# expander.net
KiCad netlist of a schematic drawn in EAGLE
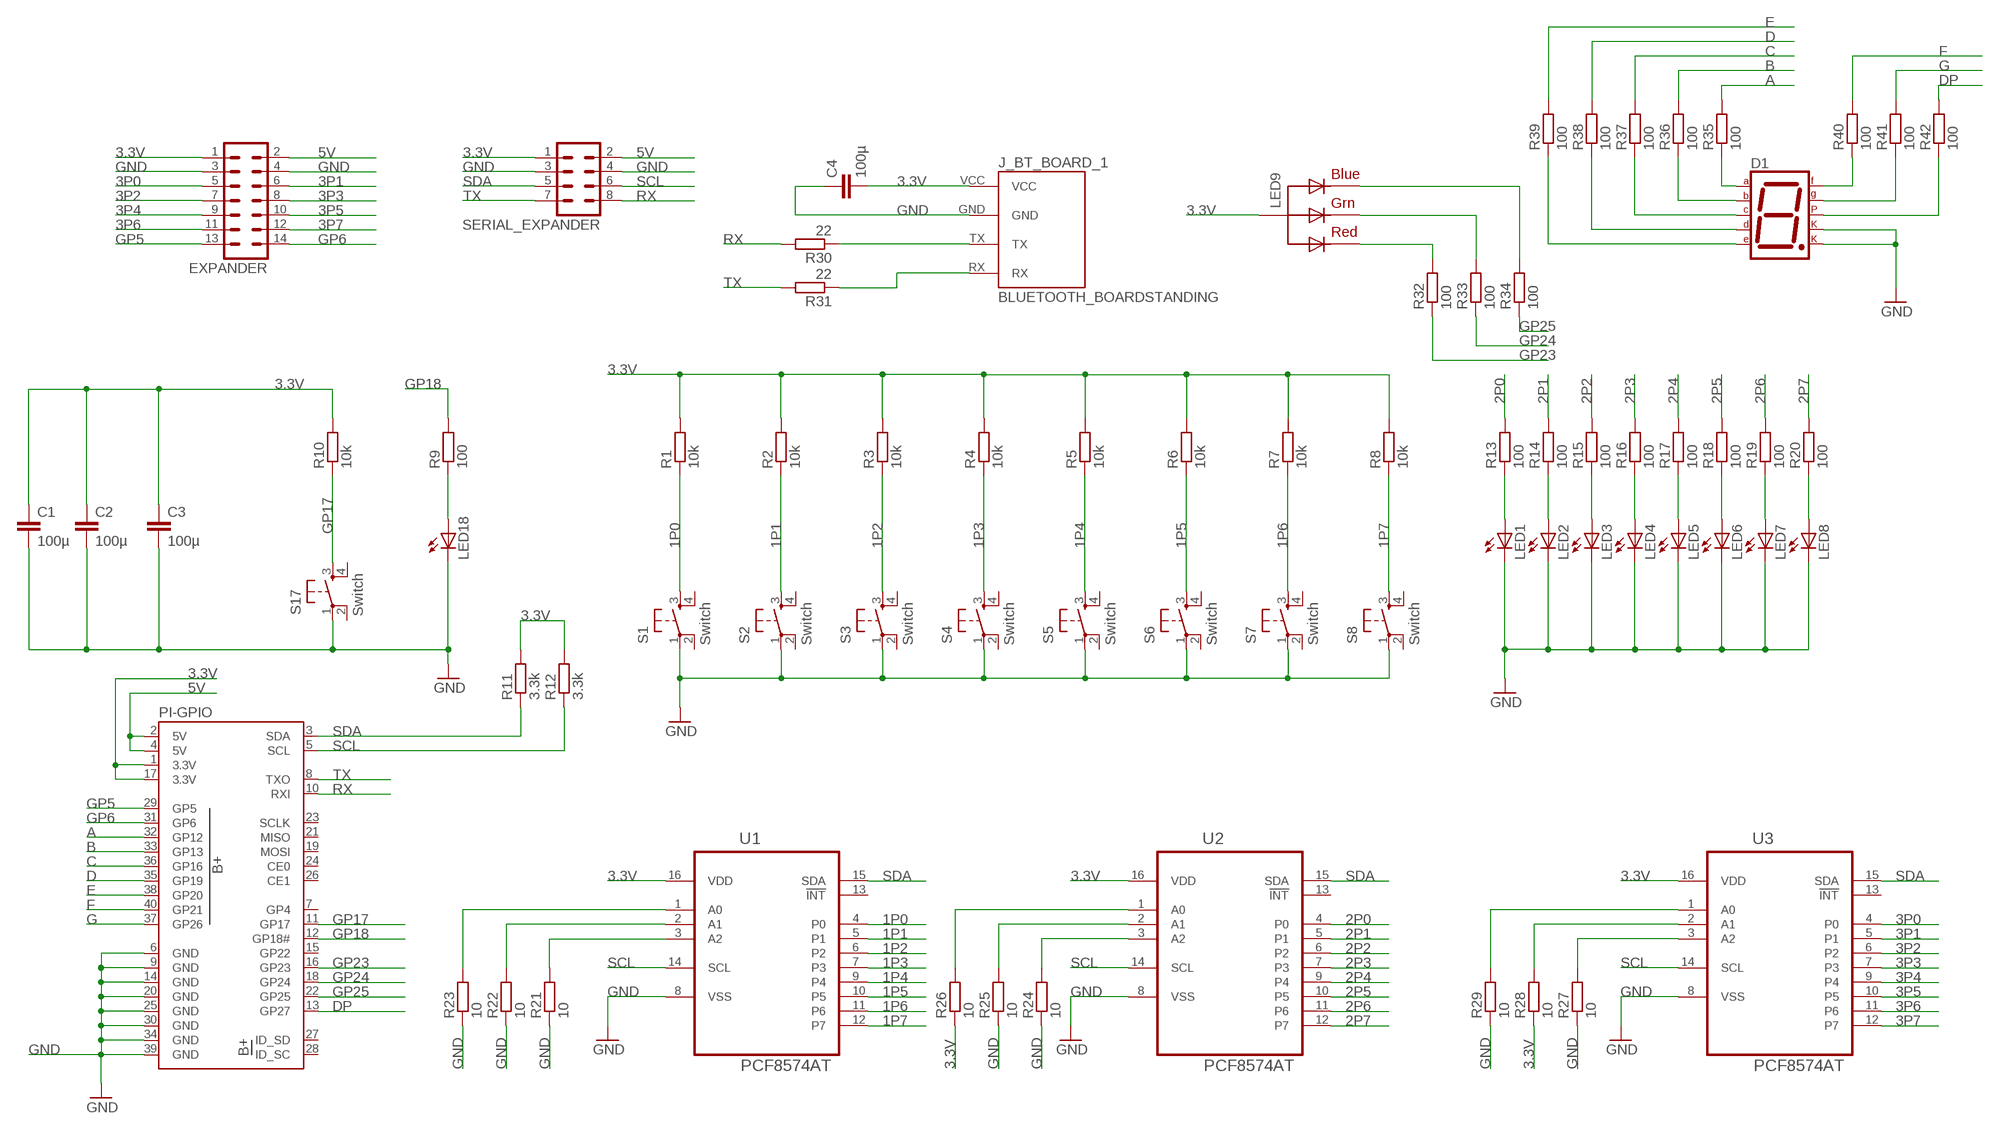
[diagram p0: schematic, sheet 1]

(export (version "E")
  (design (tool "Eeschema 10.0.6"))
  (components
    (comp (ref "C1")
      (value "100µ")
      (footprint "eagle-import:C0805")
      (libsource (lib "eagle-import") (part "C-EUC0805"))
    )
    (comp (ref "C2")
      (value "100µ")
      (footprint "eagle-import:C0805")
      (libsource (lib "eagle-import") (part "C-EUC0805"))
    )
    (comp (ref "C3")
      (value "100µ")
      (footprint "eagle-import:C0805")
      (libsource (lib "eagle-import") (part "C-EUC0805"))
    )
    (comp (ref "C4")
      (value "100µ")
      (footprint "eagle-import:C0805")
      (libsource (lib "eagle-import") (part "C-EUC0805"))
    )
    (comp (ref "D1")
      (value "7SEG-CK")
      (footprint "eagle-import:7SEG-13")
      (libsource (lib "eagle-import") (part "7SEG-CK"))
    )
    (comp (ref "EXPANDER")
      (value "MA07-2")
      (footprint "eagle-import:MA07-2")
      (libsource (lib "eagle-import") (part "MA07-2"))
    )
    (comp (ref "J_BT_BOARD_1")
      (value "BLUETOOTH_BOARDSTANDING")
      (footprint "eagle-import:BT_BOARD_FOOTPRINT_STANDING")
      (libsource (lib "eagle-import") (part "BLUETOOTH_BOARDSTANDING"))
    )
    (comp (ref "LED1")
      (value "LEDCHIP-LED0805")
      (footprint "eagle-import:CHIP-LED0805")
      (libsource (lib "eagle-import") (part "LEDCHIP-LED0805"))
    )
    (comp (ref "LED2")
      (value "LEDCHIP-LED0805")
      (footprint "eagle-import:CHIP-LED0805")
      (libsource (lib "eagle-import") (part "LEDCHIP-LED0805"))
    )
    (comp (ref "LED3")
      (value "LEDCHIP-LED0805")
      (footprint "eagle-import:CHIP-LED0805")
      (libsource (lib "eagle-import") (part "LEDCHIP-LED0805"))
    )
    (comp (ref "LED4")
      (value "LEDCHIP-LED0805")
      (footprint "eagle-import:CHIP-LED0805")
      (libsource (lib "eagle-import") (part "LEDCHIP-LED0805"))
    )
    (comp (ref "LED5")
      (value "LEDCHIP-LED0805")
      (footprint "eagle-import:CHIP-LED0805")
      (libsource (lib "eagle-import") (part "LEDCHIP-LED0805"))
    )
    (comp (ref "LED6")
      (value "LEDCHIP-LED0805")
      (footprint "eagle-import:CHIP-LED0805")
      (libsource (lib "eagle-import") (part "LEDCHIP-LED0805"))
    )
    (comp (ref "LED7")
      (value "LEDCHIP-LED0805")
      (footprint "eagle-import:CHIP-LED0805")
      (libsource (lib "eagle-import") (part "LEDCHIP-LED0805"))
    )
    (comp (ref "LED8")
      (value "LEDCHIP-LED0805")
      (footprint "eagle-import:CHIP-LED0805")
      (libsource (lib "eagle-import") (part "LEDCHIP-LED0805"))
    )
    (comp (ref "LED9")
      (value "RGBLED_CA-5MM")
      (footprint "eagle-import:LED5MMRGB")
      (libsource (lib "eagle-import") (part "RGBLED_CA-5MM"))
    )
    (comp (ref "LED18")
      (value "LEDCHIP-LED0805")
      (footprint "eagle-import:CHIP-LED0805")
      (libsource (lib "eagle-import") (part "LEDCHIP-LED0805"))
    )
    (comp (ref "PI-GPIO")
      (value "RASPBERRYPI-B+-GPIO")
      (footprint "eagle-import:2X20-SHROUDED")
      (libsource (lib "eagle-import") (part "RASPBERRYPI-B+-GPIO"))
    )
    (comp (ref "R1")
      (value "10k")
      (footprint "eagle-import:R0805")
      (libsource (lib "eagle-import") (part "R-EU_R0805"))
    )
    (comp (ref "R2")
      (value "10k")
      (footprint "eagle-import:R0805")
      (libsource (lib "eagle-import") (part "R-EU_R0805"))
    )
    (comp (ref "R3")
      (value "10k")
      (footprint "eagle-import:R0805")
      (libsource (lib "eagle-import") (part "R-EU_R0805"))
    )
    (comp (ref "R4")
      (value "10k")
      (footprint "eagle-import:R0805")
      (libsource (lib "eagle-import") (part "R-EU_R0805"))
    )
    (comp (ref "R5")
      (value "10k")
      (footprint "eagle-import:R0805")
      (libsource (lib "eagle-import") (part "R-EU_R0805"))
    )
    (comp (ref "R6")
      (value "10k")
      (footprint "eagle-import:R0805")
      (libsource (lib "eagle-import") (part "R-EU_R0805"))
    )
    (comp (ref "R7")
      (value "10k")
      (footprint "eagle-import:R0805")
      (libsource (lib "eagle-import") (part "R-EU_R0805"))
    )
    (comp (ref "R8")
      (value "10k")
      (footprint "eagle-import:R0805")
      (libsource (lib "eagle-import") (part "R-EU_R0805"))
    )
    (comp (ref "R9")
      (value "100")
      (footprint "eagle-import:R0805")
      (libsource (lib "eagle-import") (part "R-EU_R0805"))
    )
    (comp (ref "R10")
      (value "10k")
      (footprint "eagle-import:R0805")
      (libsource (lib "eagle-import") (part "R-EU_R0805"))
    )
    (comp (ref "R11")
      (value "3.3k")
      (footprint "eagle-import:R0805")
      (libsource (lib "eagle-import") (part "R-EU_R0805"))
    )
    (comp (ref "R12")
      (value "3.3k")
      (footprint "eagle-import:R0805")
      (libsource (lib "eagle-import") (part "R-EU_R0805"))
    )
    (comp (ref "R13")
      (value "100")
      (footprint "eagle-import:R0805")
      (libsource (lib "eagle-import") (part "R-EU_R0805"))
    )
    (comp (ref "R14")
      (value "100")
      (footprint "eagle-import:R0805")
      (libsource (lib "eagle-import") (part "R-EU_R0805"))
    )
    (comp (ref "R15")
      (value "100")
      (footprint "eagle-import:R0805")
      (libsource (lib "eagle-import") (part "R-EU_R0805"))
    )
    (comp (ref "R16")
      (value "100")
      (footprint "eagle-import:R0805")
      (libsource (lib "eagle-import") (part "R-EU_R0805"))
    )
    (comp (ref "R17")
      (value "100")
      (footprint "eagle-import:R0805")
      (libsource (lib "eagle-import") (part "R-EU_R0805"))
    )
    (comp (ref "R18")
      (value "100")
      (footprint "eagle-import:R0805")
      (libsource (lib "eagle-import") (part "R-EU_R0805"))
    )
    (comp (ref "R19")
      (value "100")
      (footprint "eagle-import:R0805")
      (libsource (lib "eagle-import") (part "R-EU_R0805"))
    )
    (comp (ref "R20")
      (value "100")
      (footprint "eagle-import:R0805")
      (libsource (lib "eagle-import") (part "R-EU_R0805"))
    )
    (comp (ref "R21")
      (value "10")
      (footprint "eagle-import:R0805")
      (libsource (lib "eagle-import") (part "R-EU_R0805"))
    )
    (comp (ref "R22")
      (value "10")
      (footprint "eagle-import:R0805")
      (libsource (lib "eagle-import") (part "R-EU_R0805"))
    )
    (comp (ref "R23")
      (value "10")
      (footprint "eagle-import:R0805")
      (libsource (lib "eagle-import") (part "R-EU_R0805"))
    )
    (comp (ref "R24")
      (value "10")
      (footprint "eagle-import:R0805")
      (libsource (lib "eagle-import") (part "R-EU_R0805"))
    )
    (comp (ref "R25")
      (value "10")
      (footprint "eagle-import:R0805")
      (libsource (lib "eagle-import") (part "R-EU_R0805"))
    )
    (comp (ref "R26")
      (value "10")
      (footprint "eagle-import:R0805")
      (libsource (lib "eagle-import") (part "R-EU_R0805"))
    )
    (comp (ref "R27")
      (value "10")
      (footprint "eagle-import:R0805")
      (libsource (lib "eagle-import") (part "R-EU_R0805"))
    )
    (comp (ref "R28")
      (value "10")
      (footprint "eagle-import:R0805")
      (libsource (lib "eagle-import") (part "R-EU_R0805"))
    )
    (comp (ref "R29")
      (value "10")
      (footprint "eagle-import:R0805")
      (libsource (lib "eagle-import") (part "R-EU_R0805"))
    )
    (comp (ref "R30")
      (value "22")
      (footprint "eagle-import:R0805")
      (libsource (lib "eagle-import") (part "R-EU_R0805"))
    )
    (comp (ref "R31")
      (value "22")
      (footprint "eagle-import:R0805")
      (libsource (lib "eagle-import") (part "R-EU_R0805"))
    )
    (comp (ref "R32")
      (value "100")
      (footprint "eagle-import:R0805")
      (libsource (lib "eagle-import") (part "R-EU_R0805"))
    )
    (comp (ref "R33")
      (value "100")
      (footprint "eagle-import:R0805")
      (libsource (lib "eagle-import") (part "R-EU_R0805"))
    )
    (comp (ref "R34")
      (value "100")
      (footprint "eagle-import:R0805")
      (libsource (lib "eagle-import") (part "R-EU_R0805"))
    )
    (comp (ref "R35")
      (value "100")
      (footprint "eagle-import:R0805")
      (libsource (lib "eagle-import") (part "R-EU_R0805"))
    )
    (comp (ref "R36")
      (value "100")
      (footprint "eagle-import:R0805")
      (libsource (lib "eagle-import") (part "R-EU_R0805"))
    )
    (comp (ref "R37")
      (value "100")
      (footprint "eagle-import:R0805")
      (libsource (lib "eagle-import") (part "R-EU_R0805"))
    )
    (comp (ref "R38")
      (value "100")
      (footprint "eagle-import:R0805")
      (libsource (lib "eagle-import") (part "R-EU_R0805"))
    )
    (comp (ref "R39")
      (value "100")
      (footprint "eagle-import:R0805")
      (libsource (lib "eagle-import") (part "R-EU_R0805"))
    )
    (comp (ref "R40")
      (value "100")
      (footprint "eagle-import:R0805")
      (libsource (lib "eagle-import") (part "R-EU_R0805"))
    )
    (comp (ref "R41")
      (value "100")
      (footprint "eagle-import:R0805")
      (libsource (lib "eagle-import") (part "R-EU_R0805"))
    )
    (comp (ref "R42")
      (value "100")
      (footprint "eagle-import:R0805")
      (libsource (lib "eagle-import") (part "R-EU_R0805"))
    )
    (comp (ref "S1")
      (value "Switch")
      (footprint "eagle-import:TAC-SWITCH-PTH")
      (libsource (lib "eagle-import") (part "TACTILE-SWITCH-PTH"))
    )
    (comp (ref "S2")
      (value "Switch")
      (footprint "eagle-import:TAC-SWITCH-PTH")
      (libsource (lib "eagle-import") (part "TACTILE-SWITCH-PTH"))
    )
    (comp (ref "S3")
      (value "Switch")
      (footprint "eagle-import:TAC-SWITCH-PTH")
      (libsource (lib "eagle-import") (part "TACTILE-SWITCH-PTH"))
    )
    (comp (ref "S4")
      (value "Switch")
      (footprint "eagle-import:TAC-SWITCH-PTH")
      (libsource (lib "eagle-import") (part "TACTILE-SWITCH-PTH"))
    )
    (comp (ref "S5")
      (value "Switch")
      (footprint "eagle-import:TAC-SWITCH-PTH")
      (libsource (lib "eagle-import") (part "TACTILE-SWITCH-PTH"))
    )
    (comp (ref "S6")
      (value "Switch")
      (footprint "eagle-import:TAC-SWITCH-PTH")
      (libsource (lib "eagle-import") (part "TACTILE-SWITCH-PTH"))
    )
    (comp (ref "S7")
      (value "Switch")
      (footprint "eagle-import:TAC-SWITCH-PTH")
      (libsource (lib "eagle-import") (part "TACTILE-SWITCH-PTH"))
    )
    (comp (ref "S8")
      (value "Switch")
      (footprint "eagle-import:TAC-SWITCH-PTH")
      (libsource (lib "eagle-import") (part "TACTILE-SWITCH-PTH"))
    )
    (comp (ref "S17")
      (value "Switch")
      (footprint "eagle-import:TAC-SWITCH-PTH")
      (libsource (lib "eagle-import") (part "TACTILE-SWITCH-PTH"))
    )
    (comp (ref "SERIAL_EXPANDER")
      (value "MA04-2")
      (footprint "eagle-import:MA04-2")
      (libsource (lib "eagle-import") (part "MA04-2"))
    )
    (comp (ref "U1")
      (value "PCF8574AT")
      (footprint "eagle-import:SOIC127P1032X265-16N")
      (fields (field (name "MPN") "PCF8574AT/3,512"))
      (libsource (lib "eagle-import") (part "PCF8574AT/3,512"))
    )
    (comp (ref "U2")
      (value "PCF8574AT")
      (footprint "eagle-import:SOIC127P1032X265-16N")
      (fields (field (name "MPN") "PCF8574AT/3,512"))
      (libsource (lib "eagle-import") (part "PCF8574AT/3,512"))
    )
    (comp (ref "U3")
      (value "PCF8574AT")
      (footprint "eagle-import:SOIC127P1032X265-16N")
      (fields (field (name "MPN") "PCF8574AT/3,512"))
      (libsource (lib "eagle-import") (part "PCF8574AT/3,512"))
    )
  )
  (nets
    (net (code "1") (name "/1P0") (class "Default")
      (node (ref "R1") (pin "1") (pinfunction "1_1") (pintype "passive"))
      (node (ref "S1") (pin "3") (pinfunction "3_3") (pintype "passive"))
      (node (ref "U1") (pin "4") (pinfunction "P0_4") (pintype "bidirectional"))
    )
    (net (code "2") (name "/1P1") (class "Default")
      (node (ref "R2") (pin "1") (pinfunction "1_1") (pintype "passive"))
      (node (ref "S2") (pin "3") (pinfunction "3_3") (pintype "passive"))
      (node (ref "U1") (pin "5") (pinfunction "P1_5") (pintype "bidirectional"))
    )
    (net (code "3") (name "/1P2") (class "Default")
      (node (ref "R3") (pin "1") (pinfunction "1_1") (pintype "passive"))
      (node (ref "S3") (pin "3") (pinfunction "3_3") (pintype "passive"))
      (node (ref "U1") (pin "6") (pinfunction "P2_6") (pintype "bidirectional"))
    )
    (net (code "4") (name "/1P3") (class "Default")
      (node (ref "R4") (pin "1") (pinfunction "1_1") (pintype "passive"))
      (node (ref "S4") (pin "3") (pinfunction "3_3") (pintype "passive"))
      (node (ref "U1") (pin "7") (pinfunction "P3_7") (pintype "bidirectional"))
    )
    (net (code "5") (name "/1P4") (class "Default")
      (node (ref "R5") (pin "1") (pinfunction "1_1") (pintype "passive"))
      (node (ref "S5") (pin "3") (pinfunction "3_3") (pintype "passive"))
      (node (ref "U1") (pin "9") (pinfunction "P4_9") (pintype "bidirectional"))
    )
    (net (code "6") (name "/1P5") (class "Default")
      (node (ref "R6") (pin "1") (pinfunction "1_1") (pintype "passive"))
      (node (ref "S6") (pin "3") (pinfunction "3_3") (pintype "passive"))
      (node (ref "U1") (pin "10") (pinfunction "P5_10") (pintype "bidirectional"))
    )
    (net (code "7") (name "/1P6") (class "Default")
      (node (ref "R7") (pin "1") (pinfunction "1_1") (pintype "passive"))
      (node (ref "S7") (pin "3") (pinfunction "3_3") (pintype "passive"))
      (node (ref "U1") (pin "11") (pinfunction "P6_11") (pintype "bidirectional"))
    )
    (net (code "8") (name "/1P7") (class "Default")
      (node (ref "R8") (pin "1") (pinfunction "1_1") (pintype "passive"))
      (node (ref "S8") (pin "3") (pinfunction "3_3") (pintype "passive"))
      (node (ref "U1") (pin "12") (pinfunction "P7_12") (pintype "bidirectional"))
    )
    (net (code "9") (name "/2P0") (class "Default")
      (node (ref "R13") (pin "2") (pinfunction "2_2") (pintype "passive"))
      (node (ref "U2") (pin "4") (pinfunction "P0_4") (pintype "bidirectional"))
    )
    (net (code "10") (name "/2P1") (class "Default")
      (node (ref "R14") (pin "2") (pinfunction "2_2") (pintype "passive"))
      (node (ref "U2") (pin "5") (pinfunction "P1_5") (pintype "bidirectional"))
    )
    (net (code "11") (name "/2P2") (class "Default")
      (node (ref "R15") (pin "2") (pinfunction "2_2") (pintype "passive"))
      (node (ref "U2") (pin "6") (pinfunction "P2_6") (pintype "bidirectional"))
    )
    (net (code "12") (name "/2P3") (class "Default")
      (node (ref "R16") (pin "2") (pinfunction "2_2") (pintype "passive"))
      (node (ref "U2") (pin "7") (pinfunction "P3_7") (pintype "bidirectional"))
    )
    (net (code "13") (name "/2P4") (class "Default")
      (node (ref "R17") (pin "2") (pinfunction "2_2") (pintype "passive"))
      (node (ref "U2") (pin "9") (pinfunction "P4_9") (pintype "bidirectional"))
    )
    (net (code "14") (name "/2P5") (class "Default")
      (node (ref "R18") (pin "2") (pinfunction "2_2") (pintype "passive"))
      (node (ref "U2") (pin "10") (pinfunction "P5_10") (pintype "bidirectional"))
    )
    (net (code "15") (name "/2P6") (class "Default")
      (node (ref "R19") (pin "2") (pinfunction "2_2") (pintype "passive"))
      (node (ref "U2") (pin "11") (pinfunction "P6_11") (pintype "bidirectional"))
    )
    (net (code "16") (name "/2P7") (class "Default")
      (node (ref "R20") (pin "2") (pinfunction "2_2") (pintype "passive"))
      (node (ref "U2") (pin "12") (pinfunction "P7_12") (pintype "bidirectional"))
    )
    (net (code "17") (name "/3.3V") (class "Default")
      (node (ref "C1") (pin "1") (pinfunction "1_1") (pintype "passive"))
      (node (ref "C2") (pin "1") (pinfunction "1_1") (pintype "passive"))
      (node (ref "C3") (pin "1") (pinfunction "1_1") (pintype "passive"))
      (node (ref "C4") (pin "2") (pinfunction "2_2") (pintype "passive"))
      (node (ref "EXPANDER") (pin "1") (pinfunction "1_1") (pintype "passive"))
      (node (ref "J_BT_BOARD_1") (pin "VCC") (pinfunction "VCC_VCC") (pintype "bidirectional"))
      (node (ref "LED9") (pin "2") (pinfunction "VCC_2") (pintype "bidirectional"))
      (node (ref "PI-GPIO") (pin "1") (pinfunction "3.3V_1") (pintype "power_in"))
      (node (ref "PI-GPIO") (pin "17") (pinfunction "3.3V_17") (pintype "power_in"))
      (node (ref "R1") (pin "2") (pinfunction "2_2") (pintype "passive"))
      (node (ref "R10") (pin "2") (pinfunction "2_2") (pintype "passive"))
      (node (ref "R11") (pin "2") (pinfunction "2_2") (pintype "passive"))
      (node (ref "R12") (pin "2") (pinfunction "2_2") (pintype "passive"))
      (node (ref "R2") (pin "2") (pinfunction "2_2") (pintype "passive"))
      (node (ref "R26") (pin "1") (pinfunction "1_1") (pintype "passive"))
      (node (ref "R28") (pin "1") (pinfunction "1_1") (pintype "passive"))
      (node (ref "R3") (pin "2") (pinfunction "2_2") (pintype "passive"))
      (node (ref "R4") (pin "2") (pinfunction "2_2") (pintype "passive"))
      (node (ref "R5") (pin "2") (pinfunction "2_2") (pintype "passive"))
      (node (ref "R6") (pin "2") (pinfunction "2_2") (pintype "passive"))
      (node (ref "R7") (pin "2") (pinfunction "2_2") (pintype "passive"))
      (node (ref "R8") (pin "2") (pinfunction "2_2") (pintype "passive"))
      (node (ref "SERIAL_EXPANDER") (pin "1") (pinfunction "1_1") (pintype "passive"))
      (node (ref "U1") (pin "16") (pinfunction "VDD_16") (pintype "power_in"))
      (node (ref "U2") (pin "16") (pinfunction "VDD_16") (pintype "power_in"))
      (node (ref "U3") (pin "16") (pinfunction "VDD_16") (pintype "power_in"))
    )
    (net (code "18") (name "/3P0") (class "Default")
      (node (ref "EXPANDER") (pin "5") (pinfunction "5_5") (pintype "passive"))
      (node (ref "U3") (pin "4") (pinfunction "P0_4") (pintype "bidirectional"))
    )
    (net (code "19") (name "/3P1") (class "Default")
      (node (ref "EXPANDER") (pin "6") (pinfunction "6_6") (pintype "passive"))
      (node (ref "U3") (pin "5") (pinfunction "P1_5") (pintype "bidirectional"))
    )
    (net (code "20") (name "/3P2") (class "Default")
      (node (ref "EXPANDER") (pin "7") (pinfunction "7_7") (pintype "passive"))
      (node (ref "U3") (pin "6") (pinfunction "P2_6") (pintype "bidirectional"))
    )
    (net (code "21") (name "/3P3") (class "Default")
      (node (ref "EXPANDER") (pin "8") (pinfunction "8_8") (pintype "passive"))
      (node (ref "U3") (pin "7") (pinfunction "P3_7") (pintype "bidirectional"))
    )
    (net (code "22") (name "/3P4") (class "Default")
      (node (ref "EXPANDER") (pin "9") (pinfunction "9_9") (pintype "passive"))
      (node (ref "U3") (pin "9") (pinfunction "P4_9") (pintype "bidirectional"))
    )
    (net (code "23") (name "/3P5") (class "Default")
      (node (ref "EXPANDER") (pin "10") (pinfunction "10_10") (pintype "passive"))
      (node (ref "U3") (pin "10") (pinfunction "P5_10") (pintype "bidirectional"))
    )
    (net (code "24") (name "/3P6") (class "Default")
      (node (ref "EXPANDER") (pin "11") (pinfunction "11_11") (pintype "passive"))
      (node (ref "U3") (pin "11") (pinfunction "P6_11") (pintype "bidirectional"))
    )
    (net (code "25") (name "/3P7") (class "Default")
      (node (ref "EXPANDER") (pin "12") (pinfunction "12_12") (pintype "passive"))
      (node (ref "U3") (pin "12") (pinfunction "P7_12") (pintype "bidirectional"))
    )
    (net (code "26") (name "/5V") (class "Default")
      (node (ref "EXPANDER") (pin "2") (pinfunction "2_2") (pintype "passive"))
      (node (ref "PI-GPIO") (pin "2") (pinfunction "5V_2") (pintype "power_in"))
      (node (ref "PI-GPIO") (pin "4") (pinfunction "5V_4") (pintype "power_in"))
      (node (ref "SERIAL_EXPANDER") (pin "2") (pinfunction "2_2") (pintype "passive"))
    )
    (net (code "27") (name "/A") (class "Default")
      (node (ref "PI-GPIO") (pin "32") (pinfunction "GP12_32") (pintype "bidirectional"))
      (node (ref "R35") (pin "2") (pinfunction "2_2") (pintype "passive"))
    )
    (net (code "28") (name "/B") (class "Default")
      (node (ref "PI-GPIO") (pin "33") (pinfunction "GP13_33") (pintype "bidirectional"))
      (node (ref "R36") (pin "2") (pinfunction "2_2") (pintype "passive"))
    )
    (net (code "29") (name "/C") (class "Default")
      (node (ref "PI-GPIO") (pin "36") (pinfunction "GP16_36") (pintype "bidirectional"))
      (node (ref "R37") (pin "2") (pinfunction "2_2") (pintype "passive"))
    )
    (net (code "30") (name "/D") (class "Default")
      (node (ref "PI-GPIO") (pin "35") (pinfunction "GP19_35") (pintype "bidirectional"))
      (node (ref "R38") (pin "2") (pinfunction "2_2") (pintype "passive"))
    )
    (net (code "31") (name "/DP") (class "Default")
      (node (ref "PI-GPIO") (pin "13") (pinfunction "GP27_13") (pintype "bidirectional"))
      (node (ref "R42") (pin "2") (pinfunction "2_2") (pintype "passive"))
    )
    (net (code "32") (name "/E") (class "Default")
      (node (ref "PI-GPIO") (pin "38") (pinfunction "GP20_38") (pintype "bidirectional"))
      (node (ref "R39") (pin "2") (pinfunction "2_2") (pintype "passive"))
    )
    (net (code "33") (name "/F") (class "Default")
      (node (ref "PI-GPIO") (pin "40") (pinfunction "GP21_40") (pintype "bidirectional"))
      (node (ref "R40") (pin "2") (pinfunction "2_2") (pintype "passive"))
    )
    (net (code "34") (name "/G") (class "Default")
      (node (ref "PI-GPIO") (pin "37") (pinfunction "GP26_37") (pintype "bidirectional"))
      (node (ref "R41") (pin "2") (pinfunction "2_2") (pintype "passive"))
    )
    (net (code "35") (name "/GP5") (class "Default")
      (node (ref "EXPANDER") (pin "13") (pinfunction "13_13") (pintype "passive"))
      (node (ref "PI-GPIO") (pin "29") (pinfunction "GP5_29") (pintype "bidirectional"))
    )
    (net (code "36") (name "/GP6") (class "Default")
      (node (ref "EXPANDER") (pin "14") (pinfunction "14_14") (pintype "passive"))
      (node (ref "PI-GPIO") (pin "31") (pinfunction "GP6_31") (pintype "bidirectional"))
    )
    (net (code "37") (name "/GP17") (class "Default")
      (node (ref "PI-GPIO") (pin "11") (pinfunction "GP17_11") (pintype "bidirectional"))
      (node (ref "R10") (pin "1") (pinfunction "1_1") (pintype "passive"))
      (node (ref "S17") (pin "3") (pinfunction "3_3") (pintype "passive"))
    )
    (net (code "38") (name "/GP18") (class "Default")
      (node (ref "PI-GPIO") (pin "12") (pinfunction "GP18#_12") (pintype "bidirectional"))
      (node (ref "R9") (pin "2") (pinfunction "2_2") (pintype "passive"))
    )
    (net (code "39") (name "/GP23") (class "Default")
      (node (ref "PI-GPIO") (pin "16") (pinfunction "GP23_16") (pintype "bidirectional"))
      (node (ref "R32") (pin "1") (pinfunction "1_1") (pintype "passive"))
    )
    (net (code "40") (name "/GP24") (class "Default")
      (node (ref "PI-GPIO") (pin "18") (pinfunction "GP24_18") (pintype "bidirectional"))
      (node (ref "R33") (pin "1") (pinfunction "1_1") (pintype "passive"))
    )
    (net (code "41") (name "/GP25") (class "Default")
      (node (ref "PI-GPIO") (pin "22") (pinfunction "GP25_22") (pintype "bidirectional"))
      (node (ref "R34") (pin "1") (pinfunction "1_1") (pintype "passive"))
    )
    (net (code "42") (name "/RX") (class "Default")
      (node (ref "PI-GPIO") (pin "10") (pinfunction "RXI_10") (pintype "input"))
      (node (ref "R30") (pin "2") (pinfunction "2_2") (pintype "passive"))
      (node (ref "SERIAL_EXPANDER") (pin "8") (pinfunction "8_8") (pintype "passive"))
    )
    (net (code "43") (name "/SCL") (class "Default")
      (node (ref "PI-GPIO") (pin "5") (pinfunction "SCL_5") (pintype "bidirectional"))
      (node (ref "R12") (pin "1") (pinfunction "1_1") (pintype "passive"))
      (node (ref "SERIAL_EXPANDER") (pin "6") (pinfunction "6_6") (pintype "passive"))
      (node (ref "U1") (pin "14") (pinfunction "SCL_14") (pintype "input"))
      (node (ref "U2") (pin "14") (pinfunction "SCL_14") (pintype "input"))
      (node (ref "U3") (pin "14") (pinfunction "SCL_14") (pintype "input"))
    )
    (net (code "44") (name "/SDA") (class "Default")
      (node (ref "PI-GPIO") (pin "3") (pinfunction "SDA_3") (pintype "bidirectional"))
      (node (ref "R11") (pin "1") (pinfunction "1_1") (pintype "passive"))
      (node (ref "SERIAL_EXPANDER") (pin "5") (pinfunction "5_5") (pintype "passive"))
      (node (ref "U1") (pin "15") (pinfunction "SDA_15") (pintype "bidirectional"))
      (node (ref "U2") (pin "15") (pinfunction "SDA_15") (pintype "bidirectional"))
      (node (ref "U3") (pin "15") (pinfunction "SDA_15") (pintype "bidirectional"))
    )
    (net (code "45") (name "/TX") (class "Default")
      (node (ref "PI-GPIO") (pin "8") (pinfunction "TXO_8") (pintype "output"))
      (node (ref "R31") (pin "2") (pinfunction "2_2") (pintype "passive"))
      (node (ref "SERIAL_EXPANDER") (pin "7") (pinfunction "7_7") (pintype "passive"))
    )
    (net (code "46") (name "GND") (class "Default")
      (node (ref "C1") (pin "2") (pinfunction "2_2") (pintype "passive"))
      (node (ref "C2") (pin "2") (pinfunction "2_2") (pintype "passive"))
      (node (ref "C3") (pin "2") (pinfunction "2_2") (pintype "passive"))
      (node (ref "C4") (pin "1") (pinfunction "1_1") (pintype "passive"))
      (node (ref "D1") (pin "3") (pinfunction "CK1_3") (pintype "passive"))
      (node (ref "D1") (pin "8") (pinfunction "CK2_8") (pintype "passive"))
      (node (ref "EXPANDER") (pin "3") (pinfunction "3_3") (pintype "passive"))
      (node (ref "EXPANDER") (pin "4") (pinfunction "4_4") (pintype "passive"))
      (node (ref "J_BT_BOARD_1") (pin "GND") (pinfunction "GND_GND") (pintype "bidirectional"))
      (node (ref "LED1") (pin "C") (pinfunction "C_C") (pintype "passive"))
      (node (ref "LED18") (pin "C") (pinfunction "C_C") (pintype "passive"))
      (node (ref "LED2") (pin "C") (pinfunction "C_C") (pintype "passive"))
      (node (ref "LED3") (pin "C") (pinfunction "C_C") (pintype "passive"))
      (node (ref "LED4") (pin "C") (pinfunction "C_C") (pintype "passive"))
      (node (ref "LED5") (pin "C") (pinfunction "C_C") (pintype "passive"))
      (node (ref "LED6") (pin "C") (pinfunction "C_C") (pintype "passive"))
      (node (ref "LED7") (pin "C") (pinfunction "C_C") (pintype "passive"))
      (node (ref "LED8") (pin "C") (pinfunction "C_C") (pintype "passive"))
      (node (ref "PI-GPIO") (pin "14") (pinfunction "GND_14") (pintype "power_in"))
      (node (ref "PI-GPIO") (pin "20") (pinfunction "GND_20") (pintype "power_in"))
      (node (ref "PI-GPIO") (pin "25") (pinfunction "GND_25") (pintype "power_in"))
      (node (ref "PI-GPIO") (pin "30") (pinfunction "GND_30") (pintype "power_in"))
      (node (ref "PI-GPIO") (pin "34") (pinfunction "GND_34") (pintype "power_in"))
      (node (ref "PI-GPIO") (pin "39") (pinfunction "GND_39") (pintype "power_in"))
      (node (ref "PI-GPIO") (pin "6") (pinfunction "GND_6") (pintype "power_in"))
      (node (ref "PI-GPIO") (pin "9") (pinfunction "GND_9") (pintype "power_in"))
      (node (ref "R21") (pin "1") (pinfunction "1_1") (pintype "passive"))
      (node (ref "R22") (pin "1") (pinfunction "1_1") (pintype "passive"))
      (node (ref "R23") (pin "1") (pinfunction "1_1") (pintype "passive"))
      (node (ref "R24") (pin "1") (pinfunction "1_1") (pintype "passive"))
      (node (ref "R25") (pin "1") (pinfunction "1_1") (pintype "passive"))
      (node (ref "R27") (pin "1") (pinfunction "1_1") (pintype "passive"))
      (node (ref "R29") (pin "1") (pinfunction "1_1") (pintype "passive"))
      (node (ref "S1") (pin "1") (pinfunction "1_1") (pintype "passive"))
      (node (ref "S17") (pin "1") (pinfunction "1_1") (pintype "passive"))
      (node (ref "S2") (pin "1") (pinfunction "1_1") (pintype "passive"))
      (node (ref "S3") (pin "1") (pinfunction "1_1") (pintype "passive"))
      (node (ref "S4") (pin "1") (pinfunction "1_1") (pintype "passive"))
      (node (ref "S5") (pin "1") (pinfunction "1_1") (pintype "passive"))
      (node (ref "S6") (pin "1") (pinfunction "1_1") (pintype "passive"))
      (node (ref "S7") (pin "1") (pinfunction "1_1") (pintype "passive"))
      (node (ref "S8") (pin "1") (pinfunction "1_1") (pintype "passive"))
      (node (ref "SERIAL_EXPANDER") (pin "3") (pinfunction "3_3") (pintype "passive"))
      (node (ref "SERIAL_EXPANDER") (pin "4") (pinfunction "4_4") (pintype "passive"))
      (node (ref "U1") (pin "8") (pinfunction "VSS_8") (pintype "passive"))
      (node (ref "U2") (pin "8") (pinfunction "VSS_8") (pintype "passive"))
      (node (ref "U3") (pin "8") (pinfunction "VSS_8") (pintype "passive"))
    )
    (net (code "47") (name "Net-(D1-A)") (class "Default")
      (node (ref "D1") (pin "7") (pinfunction "A_7") (pintype "passive"))
      (node (ref "R35") (pin "1") (pinfunction "1_1") (pintype "passive"))
    )
    (net (code "48") (name "Net-(D1-B)") (class "Default")
      (node (ref "D1") (pin "6") (pinfunction "B_6") (pintype "passive"))
      (node (ref "R36") (pin "1") (pinfunction "1_1") (pintype "passive"))
    )
    (net (code "49") (name "Net-(D1-C)") (class "Default")
      (node (ref "D1") (pin "4") (pinfunction "C_4") (pintype "passive"))
      (node (ref "R37") (pin "1") (pinfunction "1_1") (pintype "passive"))
    )
    (net (code "50") (name "Net-(D1-D)") (class "Default")
      (node (ref "D1") (pin "2") (pinfunction "D_2") (pintype "passive"))
      (node (ref "R38") (pin "1") (pinfunction "1_1") (pintype "passive"))
    )
    (net (code "51") (name "Net-(D1-DP)") (class "Default")
      (node (ref "D1") (pin "5") (pinfunction "DP_5") (pintype "passive"))
      (node (ref "R42") (pin "1") (pinfunction "1_1") (pintype "passive"))
    )
    (net (code "52") (name "Net-(D1-E)") (class "Default")
      (node (ref "D1") (pin "1") (pinfunction "E_1") (pintype "passive"))
      (node (ref "R39") (pin "1") (pinfunction "1_1") (pintype "passive"))
    )
    (net (code "53") (name "Net-(D1-F)") (class "Default")
      (node (ref "D1") (pin "9") (pinfunction "F_9") (pintype "passive"))
      (node (ref "R40") (pin "1") (pinfunction "1_1") (pintype "passive"))
    )
    (net (code "54") (name "Net-(D1-G)") (class "Default")
      (node (ref "D1") (pin "10") (pinfunction "G_10") (pintype "passive"))
      (node (ref "R41") (pin "1") (pinfunction "1_1") (pintype "passive"))
    )
    (net (code "55") (name "Net-(J_BT_BOARD_1-PadRX)") (class "Default")
      (node (ref "J_BT_BOARD_1") (pin "RX") (pinfunction "RX_RX") (pintype "bidirectional"))
      (node (ref "R31") (pin "1") (pinfunction "1_1") (pintype "passive"))
    )
    (net (code "56") (name "Net-(J_BT_BOARD_1-PadTX)") (class "Default")
      (node (ref "J_BT_BOARD_1") (pin "TX") (pinfunction "TX_TX") (pintype "bidirectional"))
      (node (ref "R30") (pin "1") (pinfunction "1_1") (pintype "passive"))
    )
    (net (code "57") (name "Net-(LED1-PadA)") (class "Default")
      (node (ref "LED1") (pin "A") (pinfunction "A_A") (pintype "passive"))
      (node (ref "R13") (pin "1") (pinfunction "1_1") (pintype "passive"))
    )
    (net (code "58") (name "Net-(LED2-PadA)") (class "Default")
      (node (ref "LED2") (pin "A") (pinfunction "A_A") (pintype "passive"))
      (node (ref "R14") (pin "1") (pinfunction "1_1") (pintype "passive"))
    )
    (net (code "59") (name "Net-(LED3-PadA)") (class "Default")
      (node (ref "LED3") (pin "A") (pinfunction "A_A") (pintype "passive"))
      (node (ref "R15") (pin "1") (pinfunction "1_1") (pintype "passive"))
    )
    (net (code "60") (name "Net-(LED4-PadA)") (class "Default")
      (node (ref "LED4") (pin "A") (pinfunction "A_A") (pintype "passive"))
      (node (ref "R16") (pin "1") (pinfunction "1_1") (pintype "passive"))
    )
    (net (code "61") (name "Net-(LED5-PadA)") (class "Default")
      (node (ref "LED5") (pin "A") (pinfunction "A_A") (pintype "passive"))
      (node (ref "R17") (pin "1") (pinfunction "1_1") (pintype "passive"))
    )
    (net (code "62") (name "Net-(LED6-PadA)") (class "Default")
      (node (ref "LED6") (pin "A") (pinfunction "A_A") (pintype "passive"))
      (node (ref "R18") (pin "1") (pinfunction "1_1") (pintype "passive"))
    )
    (net (code "63") (name "Net-(LED7-PadA)") (class "Default")
      (node (ref "LED7") (pin "A") (pinfunction "A_A") (pintype "passive"))
      (node (ref "R19") (pin "1") (pinfunction "1_1") (pintype "passive"))
    )
    (net (code "64") (name "Net-(LED8-PadA)") (class "Default")
      (node (ref "LED8") (pin "A") (pinfunction "A_A") (pintype "passive"))
      (node (ref "R20") (pin "1") (pinfunction "1_1") (pintype "passive"))
    )
    (net (code "65") (name "Net-(LED9-BLUE)") (class "Default")
      (node (ref "LED9") (pin "4") (pinfunction "BLUE_4") (pintype "bidirectional"))
      (node (ref "R34") (pin "2") (pinfunction "2_2") (pintype "passive"))
    )
    (net (code "66") (name "Net-(LED9-GREEN)") (class "Default")
      (node (ref "LED9") (pin "3") (pinfunction "GREEN_3") (pintype "bidirectional"))
      (node (ref "R33") (pin "2") (pinfunction "2_2") (pintype "passive"))
    )
    (net (code "67") (name "Net-(LED9-RED)") (class "Default")
      (node (ref "LED9") (pin "1") (pinfunction "RED_1") (pintype "bidirectional"))
      (node (ref "R32") (pin "2") (pinfunction "2_2") (pintype "passive"))
    )
    (net (code "68") (name "Net-(LED18-PadA)") (class "Default")
      (node (ref "LED18") (pin "A") (pinfunction "A_A") (pintype "passive"))
      (node (ref "R9") (pin "1") (pinfunction "1_1") (pintype "passive"))
    )
    (net (code "69") (name "Net-(U1-A0)") (class "Default")
      (node (ref "R23") (pin "2") (pinfunction "2_2") (pintype "passive"))
      (node (ref "U1") (pin "1") (pinfunction "A0_1") (pintype "input"))
    )
    (net (code "70") (name "Net-(U1-A1)") (class "Default")
      (node (ref "R22") (pin "2") (pinfunction "2_2") (pintype "passive"))
      (node (ref "U1") (pin "2") (pinfunction "A1_2") (pintype "input"))
    )
    (net (code "71") (name "Net-(U1-A2)") (class "Default")
      (node (ref "R21") (pin "2") (pinfunction "2_2") (pintype "passive"))
      (node (ref "U1") (pin "3") (pinfunction "A2_3") (pintype "input"))
    )
    (net (code "72") (name "Net-(U2-A0)") (class "Default")
      (node (ref "R26") (pin "2") (pinfunction "2_2") (pintype "passive"))
      (node (ref "U2") (pin "1") (pinfunction "A0_1") (pintype "input"))
    )
    (net (code "73") (name "Net-(U2-A1)") (class "Default")
      (node (ref "R25") (pin "2") (pinfunction "2_2") (pintype "passive"))
      (node (ref "U2") (pin "2") (pinfunction "A1_2") (pintype "input"))
    )
    (net (code "74") (name "Net-(U2-A2)") (class "Default")
      (node (ref "R24") (pin "2") (pinfunction "2_2") (pintype "passive"))
      (node (ref "U2") (pin "3") (pinfunction "A2_3") (pintype "input"))
    )
    (net (code "75") (name "Net-(U3-A0)") (class "Default")
      (node (ref "R29") (pin "2") (pinfunction "2_2") (pintype "passive"))
      (node (ref "U3") (pin "1") (pinfunction "A0_1") (pintype "input"))
    )
    (net (code "76") (name "Net-(U3-A1)") (class "Default")
      (node (ref "R28") (pin "2") (pinfunction "2_2") (pintype "passive"))
      (node (ref "U3") (pin "2") (pinfunction "A1_2") (pintype "input"))
    )
    (net (code "77") (name "Net-(U3-A2)") (class "Default")
      (node (ref "R27") (pin "2") (pinfunction "2_2") (pintype "passive"))
      (node (ref "U3") (pin "3") (pinfunction "A2_3") (pintype "input"))
    )
    (net (code "78") (name "unconnected-(PI-GPIO-CE0-Pad24)") (class "Default")
      (node (ref "PI-GPIO") (pin "24") (pinfunction "CE0_24") (pintype "output"))
    )
    (net (code "79") (name "unconnected-(PI-GPIO-CE1-Pad26)") (class "Default")
      (node (ref "PI-GPIO") (pin "26") (pinfunction "CE1_26") (pintype "output"))
    )
    (net (code "80") (name "unconnected-(PI-GPIO-GP4-Pad7)") (class "Default")
      (node (ref "PI-GPIO") (pin "7") (pinfunction "GP4_7") (pintype "bidirectional"))
    )
    (net (code "81") (name "unconnected-(PI-GPIO-GP22-Pad15)") (class "Default")
      (node (ref "PI-GPIO") (pin "15") (pinfunction "GP22_15") (pintype "bidirectional"))
    )
    (net (code "82") (name "unconnected-(PI-GPIO-ID_SC-Pad28)") (class "Default")
      (node (ref "PI-GPIO") (pin "28") (pinfunction "ID_SC_28") (pintype "bidirectional"))
    )
    (net (code "83") (name "unconnected-(PI-GPIO-ID_SD-Pad27)") (class "Default")
      (node (ref "PI-GPIO") (pin "27") (pinfunction "ID_SD_27") (pintype "bidirectional"))
    )
    (net (code "84") (name "unconnected-(PI-GPIO-MISO-Pad21)") (class "Default")
      (node (ref "PI-GPIO") (pin "21") (pinfunction "MISO_21") (pintype "input"))
    )
    (net (code "85") (name "unconnected-(PI-GPIO-MOSI-Pad19)") (class "Default")
      (node (ref "PI-GPIO") (pin "19") (pinfunction "MOSI_19") (pintype "output"))
    )
    (net (code "86") (name "unconnected-(PI-GPIO-SCLK-Pad23)") (class "Default")
      (node (ref "PI-GPIO") (pin "23") (pinfunction "SCLK_23") (pintype "output"))
    )
    (net (code "87") (name "unconnected-(S1-Pad2)") (class "Default")
      (node (ref "S1") (pin "2") (pinfunction "2_2") (pintype "passive"))
    )
    (net (code "88") (name "unconnected-(S1-Pad4)") (class "Default")
      (node (ref "S1") (pin "4") (pinfunction "4_4") (pintype "passive"))
    )
    (net (code "89") (name "unconnected-(S2-Pad2)") (class "Default")
      (node (ref "S2") (pin "2") (pinfunction "2_2") (pintype "passive"))
    )
    (net (code "90") (name "unconnected-(S2-Pad4)") (class "Default")
      (node (ref "S2") (pin "4") (pinfunction "4_4") (pintype "passive"))
    )
    (net (code "91") (name "unconnected-(S3-Pad2)") (class "Default")
      (node (ref "S3") (pin "2") (pinfunction "2_2") (pintype "passive"))
    )
    (net (code "92") (name "unconnected-(S3-Pad4)") (class "Default")
      (node (ref "S3") (pin "4") (pinfunction "4_4") (pintype "passive"))
    )
    (net (code "93") (name "unconnected-(S4-Pad2)") (class "Default")
      (node (ref "S4") (pin "2") (pinfunction "2_2") (pintype "passive"))
    )
    (net (code "94") (name "unconnected-(S4-Pad4)") (class "Default")
      (node (ref "S4") (pin "4") (pinfunction "4_4") (pintype "passive"))
    )
    (net (code "95") (name "unconnected-(S5-Pad2)") (class "Default")
      (node (ref "S5") (pin "2") (pinfunction "2_2") (pintype "passive"))
    )
    (net (code "96") (name "unconnected-(S5-Pad4)") (class "Default")
      (node (ref "S5") (pin "4") (pinfunction "4_4") (pintype "passive"))
    )
    (net (code "97") (name "unconnected-(S6-Pad2)") (class "Default")
      (node (ref "S6") (pin "2") (pinfunction "2_2") (pintype "passive"))
    )
    (net (code "98") (name "unconnected-(S6-Pad4)") (class "Default")
      (node (ref "S6") (pin "4") (pinfunction "4_4") (pintype "passive"))
    )
    (net (code "99") (name "unconnected-(S7-Pad2)") (class "Default")
      (node (ref "S7") (pin "2") (pinfunction "2_2") (pintype "passive"))
    )
    (net (code "100") (name "unconnected-(S7-Pad4)") (class "Default")
      (node (ref "S7") (pin "4") (pinfunction "4_4") (pintype "passive"))
    )
    (net (code "101") (name "unconnected-(S8-Pad2)") (class "Default")
      (node (ref "S8") (pin "2") (pinfunction "2_2") (pintype "passive"))
    )
    (net (code "102") (name "unconnected-(S8-Pad4)") (class "Default")
      (node (ref "S8") (pin "4") (pinfunction "4_4") (pintype "passive"))
    )
    (net (code "103") (name "unconnected-(S17-Pad2)") (class "Default")
      (node (ref "S17") (pin "2") (pinfunction "2_2") (pintype "passive"))
    )
    (net (code "104") (name "unconnected-(S17-Pad4)") (class "Default")
      (node (ref "S17") (pin "4") (pinfunction "4_4") (pintype "passive"))
    )
    (net (code "105") (name "unconnected-(U1-~{INT}-Pad13)") (class "Default")
      (node (ref "U1") (pin "13") (pinfunction "~{INT}_13") (pintype "output"))
    )
    (net (code "106") (name "unconnected-(U2-~{INT}-Pad13)") (class "Default")
      (node (ref "U2") (pin "13") (pinfunction "~{INT}_13") (pintype "output"))
    )
    (net (code "107") (name "unconnected-(U3-~{INT}-Pad13)") (class "Default")
      (node (ref "U3") (pin "13") (pinfunction "~{INT}_13") (pintype "output"))
    )
  )
)
